# VFD-IV-25-5x7x2.net
KiCad netlist of a schematic drawn in EAGLE
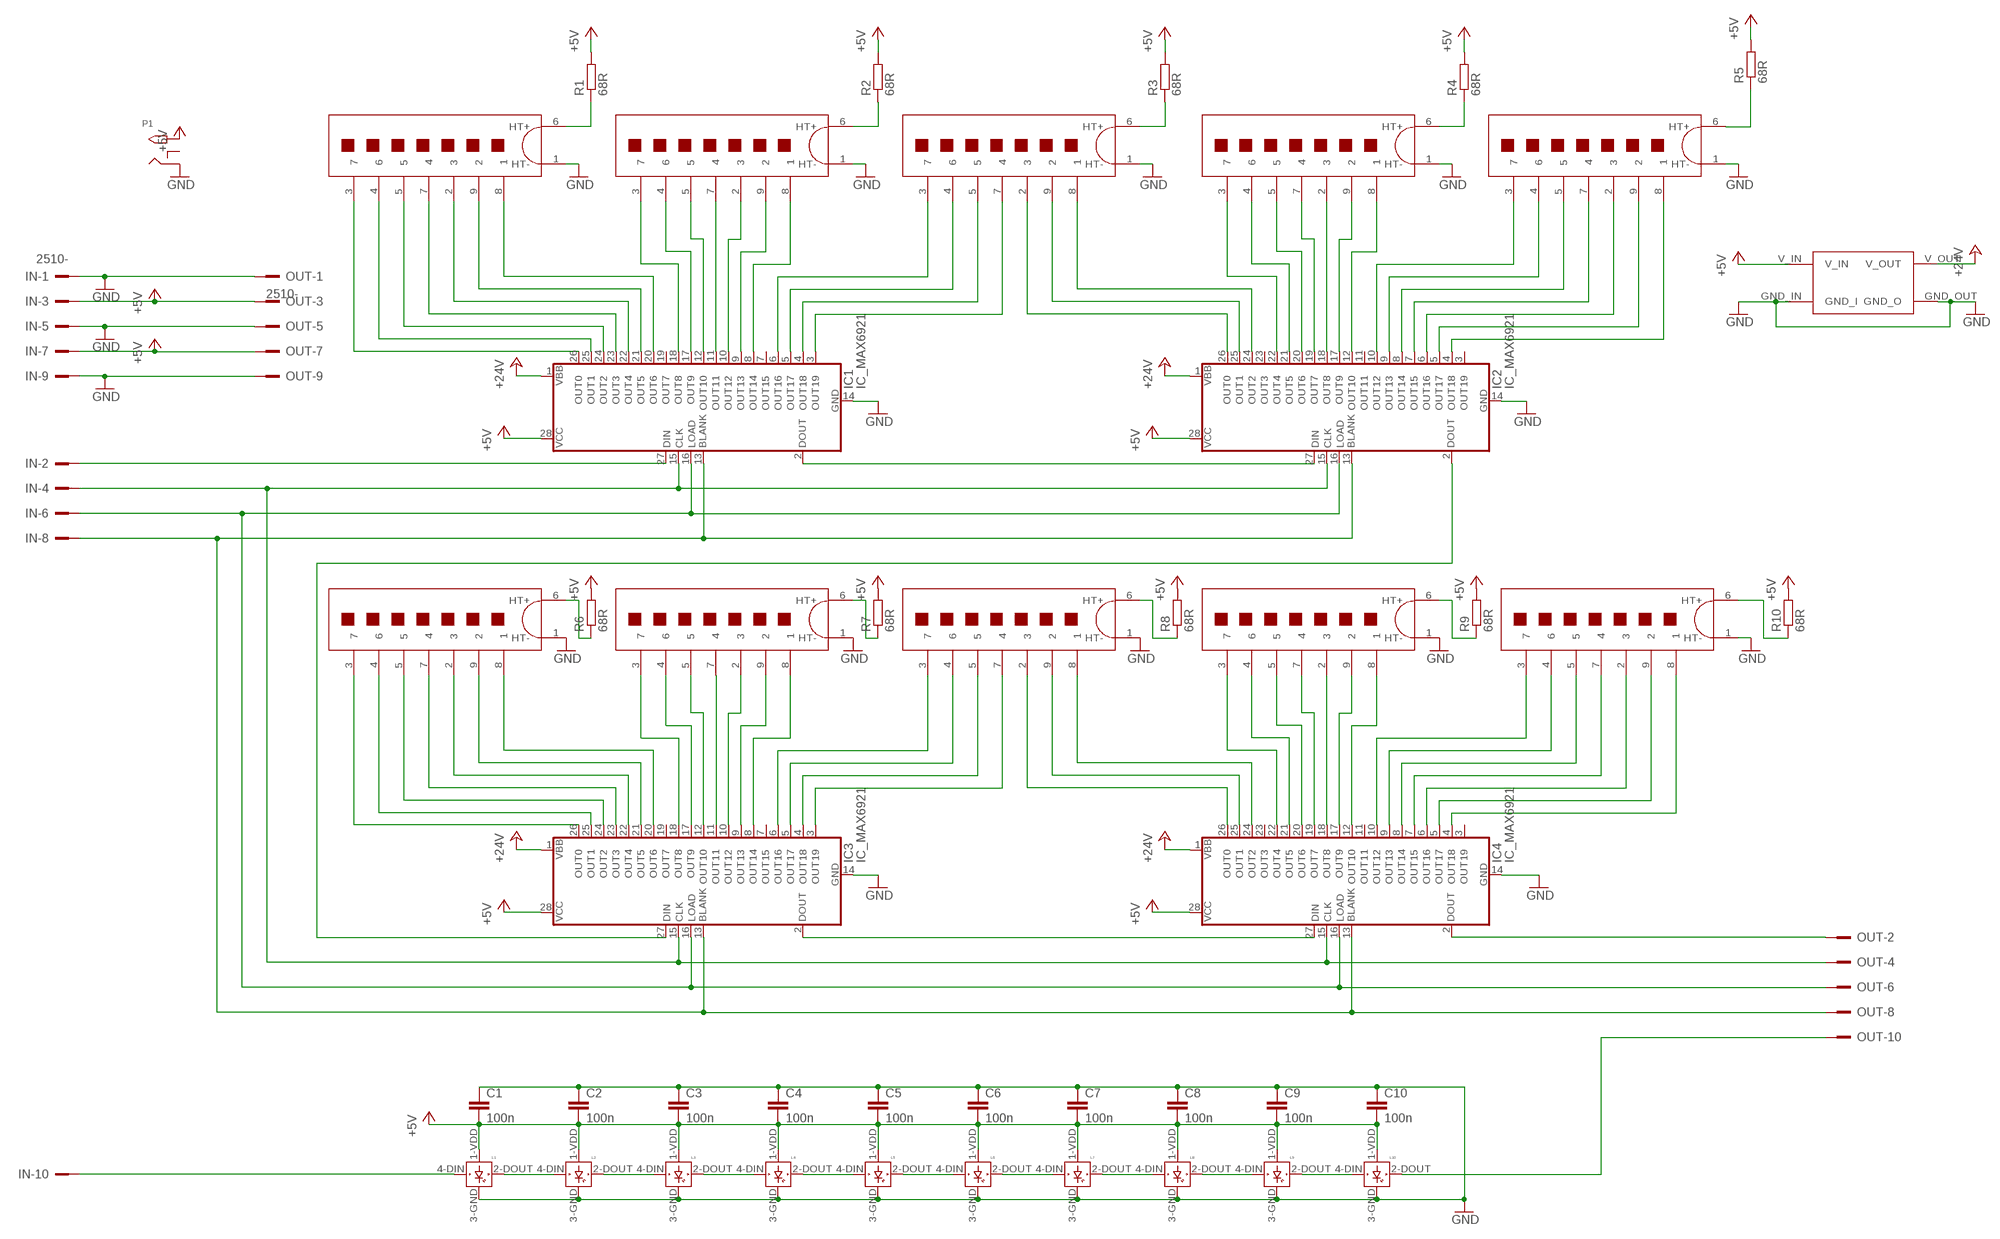
[diagram p0: schematic, sheet 1]

(export (version "E")
  (design (tool "Eeschema 10.0.6"))
  (components
    (comp (ref "1")
      (value "IV-25_DISP")
      (footprint "eagle-import:IV-25")
      (libsource (lib "eagle-import") (part "IV-25_DISP"))
    )
    (comp (ref "2")
      (value "IV-25_DISP")
      (footprint "eagle-import:IV-25")
      (libsource (lib "eagle-import") (part "IV-25_DISP"))
    )
    (comp (ref "3")
      (value "IV-25_DISP")
      (footprint "eagle-import:IV-25")
      (libsource (lib "eagle-import") (part "IV-25_DISP"))
    )
    (comp (ref "4")
      (value "IV-25_DISP")
      (footprint "eagle-import:IV-25")
      (libsource (lib "eagle-import") (part "IV-25_DISP"))
    )
    (comp (ref "5")
      (value "IV-25_DISP")
      (footprint "eagle-import:IV-25")
      (libsource (lib "eagle-import") (part "IV-25_DISP"))
    )
    (comp (ref "6")
      (value "IV-25_DISP")
      (footprint "eagle-import:IV-25")
      (libsource (lib "eagle-import") (part "IV-25_DISP"))
    )
    (comp (ref "7")
      (value "IV-25_DISP")
      (footprint "eagle-import:IV-25")
      (libsource (lib "eagle-import") (part "IV-25_DISP"))
    )
    (comp (ref "8")
      (value "IV-25_DISP")
      (footprint "eagle-import:IV-25")
      (libsource (lib "eagle-import") (part "IV-25_DISP"))
    )
    (comp (ref "9")
      (value "IV-25_DISP")
      (footprint "eagle-import:IV-25")
      (libsource (lib "eagle-import") (part "IV-25_DISP"))
    )
    (comp (ref "10")
      (value "IV-25_DISP")
      (footprint "eagle-import:IV-25")
      (libsource (lib "eagle-import") (part "IV-25_DISP"))
    )
    (comp (ref "C1")
      (value "100n")
      (footprint "eagle-import:C050-025X075")
      (libsource (lib "eagle-import") (part "C-EU050-025X075"))
    )
    (comp (ref "C2")
      (value "100n")
      (footprint "eagle-import:C050-025X075")
      (libsource (lib "eagle-import") (part "C-EU050-025X075"))
    )
    (comp (ref "C3")
      (value "100n")
      (footprint "eagle-import:C050-025X075")
      (libsource (lib "eagle-import") (part "C-EU050-025X075"))
    )
    (comp (ref "C4")
      (value "100n")
      (footprint "eagle-import:C050-025X075")
      (libsource (lib "eagle-import") (part "C-EU050-025X075"))
    )
    (comp (ref "C5")
      (value "100n")
      (footprint "eagle-import:C050-025X075")
      (libsource (lib "eagle-import") (part "C-EU050-025X075"))
    )
    (comp (ref "C6")
      (value "100n")
      (footprint "eagle-import:C050-025X075")
      (libsource (lib "eagle-import") (part "C-EU050-025X075"))
    )
    (comp (ref "C7")
      (value "100n")
      (footprint "eagle-import:C050-025X075")
      (libsource (lib "eagle-import") (part "C-EU050-025X075"))
    )
    (comp (ref "C8")
      (value "100n")
      (footprint "eagle-import:C050-025X075")
      (libsource (lib "eagle-import") (part "C-EU050-025X075"))
    )
    (comp (ref "C9")
      (value "100n")
      (footprint "eagle-import:C050-025X075")
      (libsource (lib "eagle-import") (part "C-EU050-025X075"))
    )
    (comp (ref "C10")
      (value "100n")
      (footprint "eagle-import:C050-025X075")
      (libsource (lib "eagle-import") (part "C-EU050-025X075"))
    )
    (comp (ref "IC1")
      (value "IC_MAX6921")
      (footprint "eagle-import:S28")
      (libsource (lib "eagle-import") (part "IC_MAX6921"))
    )
    (comp (ref "IC2")
      (value "IC_MAX6921")
      (footprint "eagle-import:S28")
      (libsource (lib "eagle-import") (part "IC_MAX6921"))
    )
    (comp (ref "IC3")
      (value "IC_MAX6921")
      (footprint "eagle-import:S28")
      (libsource (lib "eagle-import") (part "IC_MAX6921"))
    )
    (comp (ref "IC4")
      (value "IC_MAX6921")
      (footprint "eagle-import:S28")
      (libsource (lib "eagle-import") (part "IC_MAX6921"))
    )
    (comp (ref "IN")
      (value "2510-")
      (footprint "eagle-import:PAK100_2500-10")
      (fields (field (name "MF") "3M") (field (name "MPN") "2510-6002UB"))
      (libsource (lib "eagle-import") (part "2510-"))
    )
    (comp (ref "L1")
      (value "WS2812B")
      (footprint "eagle-import:WS2812B")
      (libsource (lib "eagle-import") (part "WS2812B"))
    )
    (comp (ref "L2")
      (value "WS2812B")
      (footprint "eagle-import:WS2812B")
      (libsource (lib "eagle-import") (part "WS2812B"))
    )
    (comp (ref "L3")
      (value "WS2812B")
      (footprint "eagle-import:WS2812B")
      (libsource (lib "eagle-import") (part "WS2812B"))
    )
    (comp (ref "L4")
      (value "WS2812B")
      (footprint "eagle-import:WS2812B")
      (libsource (lib "eagle-import") (part "WS2812B"))
    )
    (comp (ref "L5")
      (value "WS2812B")
      (footprint "eagle-import:WS2812B")
      (libsource (lib "eagle-import") (part "WS2812B"))
    )
    (comp (ref "L6")
      (value "WS2812B")
      (footprint "eagle-import:WS2812B")
      (libsource (lib "eagle-import") (part "WS2812B"))
    )
    (comp (ref "L7")
      (value "WS2812B")
      (footprint "eagle-import:WS2812B")
      (libsource (lib "eagle-import") (part "WS2812B"))
    )
    (comp (ref "L8")
      (value "WS2812B")
      (footprint "eagle-import:WS2812B")
      (libsource (lib "eagle-import") (part "WS2812B"))
    )
    (comp (ref "L9")
      (value "WS2812B")
      (footprint "eagle-import:WS2812B")
      (libsource (lib "eagle-import") (part "WS2812B"))
    )
    (comp (ref "L10")
      (value "WS2812B")
      (footprint "eagle-import:WS2812B")
      (libsource (lib "eagle-import") (part "WS2812B"))
    )
    (comp (ref "OUT")
      (value "2510-")
      (footprint "eagle-import:PAK100_2500-10")
      (fields (field (name "MF") "3M") (field (name "MPN") "2510-6002UB"))
      (libsource (lib "eagle-import") (part "2510-"))
    )
    (comp (ref "P1")
      (value "2.1MMJACKTHM")
      (footprint "eagle-import:PJ-102A")
      (libsource (lib "eagle-import") (part "2.1MMJACKTHM"))
    )
    (comp (ref "R1")
      (value "68R")
      (footprint "eagle-import:0207_10")
      (libsource (lib "eagle-import") (part "R-EU_0207/10"))
    )
    (comp (ref "R2")
      (value "68R")
      (footprint "eagle-import:0207_10")
      (libsource (lib "eagle-import") (part "R-EU_0207/10"))
    )
    (comp (ref "R3")
      (value "68R")
      (footprint "eagle-import:0207_10")
      (libsource (lib "eagle-import") (part "R-EU_0207/10"))
    )
    (comp (ref "R4")
      (value "68R")
      (footprint "eagle-import:0207_10")
      (libsource (lib "eagle-import") (part "R-EU_0207/10"))
    )
    (comp (ref "R5")
      (value "68R")
      (footprint "eagle-import:0207_10")
      (libsource (lib "eagle-import") (part "R-EU_0207/10"))
    )
    (comp (ref "R6")
      (value "68R")
      (footprint "eagle-import:0207_10")
      (libsource (lib "eagle-import") (part "R-EU_0207/10"))
    )
    (comp (ref "R7")
      (value "68R")
      (footprint "eagle-import:0207_10")
      (libsource (lib "eagle-import") (part "R-EU_0207/10"))
    )
    (comp (ref "R8")
      (value "68R")
      (footprint "eagle-import:0207_10")
      (libsource (lib "eagle-import") (part "R-EU_0207/10"))
    )
    (comp (ref "R9")
      (value "68R")
      (footprint "eagle-import:0207_10")
      (libsource (lib "eagle-import") (part "R-EU_0207/10"))
    )
    (comp (ref "R10")
      (value "68R")
      (footprint "eagle-import:0207_10")
      (libsource (lib "eagle-import") (part "R-EU_0207/10"))
    )
    (comp (ref "U$11")
      (value "STEP_UP_MODULE")
      (footprint "eagle-import:STEP_UP_MODULE")
      (libsource (lib "eagle-import") (part "STEP_UP_MODULE"))
    )
  )
  (nets
    (net (code "1") (name "+5V") (class "Default")
      (node (ref "C1") (pin "2") (pinfunction "2_2") (pintype "passive"))
      (node (ref "C10") (pin "2") (pinfunction "2_2") (pintype "passive"))
      (node (ref "C2") (pin "2") (pinfunction "2_2") (pintype "passive"))
      (node (ref "C3") (pin "2") (pinfunction "2_2") (pintype "passive"))
      (node (ref "C4") (pin "2") (pinfunction "2_2") (pintype "passive"))
      (node (ref "C5") (pin "2") (pinfunction "2_2") (pintype "passive"))
      (node (ref "C6") (pin "2") (pinfunction "2_2") (pintype "passive"))
      (node (ref "C7") (pin "2") (pinfunction "2_2") (pintype "passive"))
      (node (ref "C8") (pin "2") (pinfunction "2_2") (pintype "passive"))
      (node (ref "C9") (pin "2") (pinfunction "2_2") (pintype "passive"))
      (node (ref "IC1") (pin "28") (pinfunction "VCC_28") (pintype "power_in"))
      (node (ref "IC2") (pin "28") (pinfunction "VCC_28") (pintype "power_in"))
      (node (ref "IC3") (pin "28") (pinfunction "VCC_28") (pintype "power_in"))
      (node (ref "IC4") (pin "28") (pinfunction "VCC_28") (pintype "power_in"))
      (node (ref "IN") (pin "3") (pinfunction "KL_3") (pintype "passive"))
      (node (ref "IN") (pin "7") (pinfunction "KL_7") (pintype "passive"))
      (node (ref "L1") (pin "1-VDD") (pinfunction "VDD_1-VDD") (pintype "bidirectional"))
      (node (ref "L10") (pin "1-VDD") (pinfunction "VDD_1-VDD") (pintype "bidirectional"))
      (node (ref "L2") (pin "1-VDD") (pinfunction "VDD_1-VDD") (pintype "bidirectional"))
      (node (ref "L3") (pin "1-VDD") (pinfunction "VDD_1-VDD") (pintype "bidirectional"))
      (node (ref "L4") (pin "1-VDD") (pinfunction "VDD_1-VDD") (pintype "bidirectional"))
      (node (ref "L5") (pin "1-VDD") (pinfunction "VDD_1-VDD") (pintype "bidirectional"))
      (node (ref "L6") (pin "1-VDD") (pinfunction "VDD_1-VDD") (pintype "bidirectional"))
      (node (ref "L7") (pin "1-VDD") (pinfunction "VDD_1-VDD") (pintype "bidirectional"))
      (node (ref "L8") (pin "1-VDD") (pinfunction "VDD_1-VDD") (pintype "bidirectional"))
      (node (ref "L9") (pin "1-VDD") (pinfunction "VDD_1-VDD") (pintype "bidirectional"))
      (node (ref "OUT") (pin "3") (pinfunction "KL_3") (pintype "passive"))
      (node (ref "OUT") (pin "7") (pinfunction "KL_7") (pintype "passive"))
      (node (ref "P1") (pin "TIP") (pinfunction "TIP_TIP") (pintype "bidirectional"))
      (node (ref "R1") (pin "2") (pinfunction "2_2") (pintype "passive"))
      (node (ref "R10") (pin "2") (pinfunction "2_2") (pintype "passive"))
      (node (ref "R2") (pin "2") (pinfunction "2_2") (pintype "passive"))
      (node (ref "R3") (pin "2") (pinfunction "2_2") (pintype "passive"))
      (node (ref "R4") (pin "2") (pinfunction "2_2") (pintype "passive"))
      (node (ref "R5") (pin "2") (pinfunction "2_2") (pintype "passive"))
      (node (ref "R6") (pin "2") (pinfunction "2_2") (pintype "passive"))
      (node (ref "R7") (pin "2") (pinfunction "2_2") (pintype "passive"))
      (node (ref "R8") (pin "2") (pinfunction "2_2") (pintype "passive"))
      (node (ref "R9") (pin "2") (pinfunction "2_2") (pintype "passive"))
      (node (ref "U$11") (pin "V_IN") (pinfunction "V_IN_V_IN") (pintype "power_in"))
    )
    (net (code "2") (name "+24V") (class "Default")
      (node (ref "IC1") (pin "1") (pinfunction "VBB_1") (pintype "power_in"))
      (node (ref "IC2") (pin "1") (pinfunction "VBB_1") (pintype "power_in"))
      (node (ref "IC3") (pin "1") (pinfunction "VBB_1") (pintype "power_in"))
      (node (ref "IC4") (pin "1") (pinfunction "VBB_1") (pintype "power_in"))
      (node (ref "U$11") (pin "V_OUT") (pinfunction "V_OUT_V_OUT") (pintype "power_in"))
    )
    (net (code "3") (name "GND") (class "Default")
      (node (ref "1") (pin "1") (pinfunction "HT-_1") (pintype "power_in"))
      (node (ref "10") (pin "1") (pinfunction "HT-_1") (pintype "power_in"))
      (node (ref "2") (pin "1") (pinfunction "HT-_1") (pintype "power_in"))
      (node (ref "3") (pin "1") (pinfunction "HT-_1") (pintype "power_in"))
      (node (ref "4") (pin "1") (pinfunction "HT-_1") (pintype "power_in"))
      (node (ref "5") (pin "1") (pinfunction "HT-_1") (pintype "power_in"))
      (node (ref "6") (pin "1") (pinfunction "HT-_1") (pintype "power_in"))
      (node (ref "7") (pin "1") (pinfunction "HT-_1") (pintype "power_in"))
      (node (ref "8") (pin "1") (pinfunction "HT-_1") (pintype "power_in"))
      (node (ref "9") (pin "1") (pinfunction "HT-_1") (pintype "power_in"))
      (node (ref "C1") (pin "1") (pinfunction "1_1") (pintype "passive"))
      (node (ref "C10") (pin "1") (pinfunction "1_1") (pintype "passive"))
      (node (ref "C2") (pin "1") (pinfunction "1_1") (pintype "passive"))
      (node (ref "C3") (pin "1") (pinfunction "1_1") (pintype "passive"))
      (node (ref "C4") (pin "1") (pinfunction "1_1") (pintype "passive"))
      (node (ref "C5") (pin "1") (pinfunction "1_1") (pintype "passive"))
      (node (ref "C6") (pin "1") (pinfunction "1_1") (pintype "passive"))
      (node (ref "C7") (pin "1") (pinfunction "1_1") (pintype "passive"))
      (node (ref "C8") (pin "1") (pinfunction "1_1") (pintype "passive"))
      (node (ref "C9") (pin "1") (pinfunction "1_1") (pintype "passive"))
      (node (ref "IC1") (pin "14") (pinfunction "GND_14") (pintype "power_in"))
      (node (ref "IC2") (pin "14") (pinfunction "GND_14") (pintype "power_in"))
      (node (ref "IC3") (pin "14") (pinfunction "GND_14") (pintype "power_in"))
      (node (ref "IC4") (pin "14") (pinfunction "GND_14") (pintype "power_in"))
      (node (ref "IN") (pin "1") (pinfunction "KL_1") (pintype "passive"))
      (node (ref "IN") (pin "5") (pinfunction "KL_5") (pintype "passive"))
      (node (ref "IN") (pin "9") (pinfunction "KL_9") (pintype "passive"))
      (node (ref "L1") (pin "3-GND") (pinfunction "GND_3-GND") (pintype "bidirectional"))
      (node (ref "L10") (pin "3-GND") (pinfunction "GND_3-GND") (pintype "bidirectional"))
      (node (ref "L2") (pin "3-GND") (pinfunction "GND_3-GND") (pintype "bidirectional"))
      (node (ref "L3") (pin "3-GND") (pinfunction "GND_3-GND") (pintype "bidirectional"))
      (node (ref "L4") (pin "3-GND") (pinfunction "GND_3-GND") (pintype "bidirectional"))
      (node (ref "L5") (pin "3-GND") (pinfunction "GND_3-GND") (pintype "bidirectional"))
      (node (ref "L6") (pin "3-GND") (pinfunction "GND_3-GND") (pintype "bidirectional"))
      (node (ref "L7") (pin "3-GND") (pinfunction "GND_3-GND") (pintype "bidirectional"))
      (node (ref "L8") (pin "3-GND") (pinfunction "GND_3-GND") (pintype "bidirectional"))
      (node (ref "L9") (pin "3-GND") (pinfunction "GND_3-GND") (pintype "bidirectional"))
      (node (ref "OUT") (pin "1") (pinfunction "KL_1") (pintype "passive"))
      (node (ref "OUT") (pin "5") (pinfunction "KL_5") (pintype "passive"))
      (node (ref "OUT") (pin "9") (pinfunction "KL_9") (pintype "passive"))
      (node (ref "P1") (pin "RING") (pinfunction "RING_RING") (pintype "bidirectional"))
      (node (ref "U$11") (pin "GND_IN") (pinfunction "GND_I_GND_IN") (pintype "power_in"))
      (node (ref "U$11") (pin "GND_OUT") (pinfunction "GND_O_GND_OUT") (pintype "power_in"))
    )
    (net (code "4") (name "Net-(1-1)") (class "Default")
      (node (ref "1") (pin "8") (pinfunction "1_8") (pintype "input"))
      (node (ref "IC1") (pin "20") (pinfunction "OUT6_20") (pintype "output"))
    )
    (net (code "5") (name "Net-(1-2)") (class "Default")
      (node (ref "1") (pin "9") (pinfunction "2_9") (pintype "input"))
      (node (ref "IC1") (pin "21") (pinfunction "OUT5_21") (pintype "output"))
    )
    (net (code "6") (name "Net-(1-3)") (class "Default")
      (node (ref "1") (pin "2") (pinfunction "3_2") (pintype "input"))
      (node (ref "IC1") (pin "22") (pinfunction "OUT4_22") (pintype "output"))
    )
    (net (code "7") (name "Net-(1-4)") (class "Default")
      (node (ref "1") (pin "7") (pinfunction "4_7") (pintype "input"))
      (node (ref "IC1") (pin "23") (pinfunction "OUT3_23") (pintype "output"))
    )
    (net (code "8") (name "Net-(1-6)") (class "Default")
      (node (ref "1") (pin "4") (pinfunction "6_4") (pintype "input"))
      (node (ref "IC1") (pin "25") (pinfunction "OUT1_25") (pintype "output"))
    )
    (net (code "9") (name "Net-(1-7)") (class "Default")
      (node (ref "1") (pin "3") (pinfunction "7_3") (pintype "input"))
      (node (ref "IC1") (pin "26") (pinfunction "OUT0_26") (pintype "output"))
    )
    (net (code "10") (name "Net-(1-HT+)") (class "Default")
      (node (ref "1") (pin "6") (pinfunction "HT+_6") (pintype "power_in"))
      (node (ref "R1") (pin "1") (pinfunction "1_1") (pintype "passive"))
    )
    (net (code "11") (name "Net-(2-1)") (class "Default")
      (node (ref "2") (pin "8") (pinfunction "1_8") (pintype "input"))
      (node (ref "IC1") (pin "8") (pinfunction "OUT14_8") (pintype "output"))
    )
    (net (code "12") (name "Net-(2-2)") (class "Default")
      (node (ref "2") (pin "9") (pinfunction "2_9") (pintype "input"))
      (node (ref "IC1") (pin "9") (pinfunction "OUT13_9") (pintype "output"))
    )
    (net (code "13") (name "Net-(2-3)") (class "Default")
      (node (ref "2") (pin "2") (pinfunction "3_2") (pintype "input"))
      (node (ref "IC1") (pin "10") (pinfunction "OUT12_10") (pintype "output"))
    )
    (net (code "14") (name "Net-(2-4)") (class "Default")
      (node (ref "2") (pin "7") (pinfunction "4_7") (pintype "input"))
      (node (ref "IC1") (pin "11") (pinfunction "OUT11_11") (pintype "output"))
    )
    (net (code "15") (name "Net-(2-6)") (class "Default")
      (node (ref "2") (pin "4") (pinfunction "6_4") (pintype "input"))
      (node (ref "IC1") (pin "17") (pinfunction "OUT9_17") (pintype "output"))
    )
    (net (code "16") (name "Net-(2-7)") (class "Default")
      (node (ref "2") (pin "3") (pinfunction "7_3") (pintype "input"))
      (node (ref "IC1") (pin "18") (pinfunction "OUT8_18") (pintype "output"))
    )
    (net (code "17") (name "Net-(2-HT+)") (class "Default")
      (node (ref "2") (pin "6") (pinfunction "HT+_6") (pintype "power_in"))
      (node (ref "R2") (pin "1") (pinfunction "1_1") (pintype "passive"))
    )
    (net (code "18") (name "Net-(3-1)") (class "Default")
      (node (ref "3") (pin "8") (pinfunction "1_8") (pintype "input"))
      (node (ref "IC2") (pin "24") (pinfunction "OUT2_24") (pintype "output"))
    )
    (net (code "19") (name "Net-(3-2)") (class "Default")
      (node (ref "3") (pin "9") (pinfunction "2_9") (pintype "input"))
      (node (ref "IC2") (pin "25") (pinfunction "OUT1_25") (pintype "output"))
    )
    (net (code "20") (name "Net-(3-3)") (class "Default")
      (node (ref "3") (pin "2") (pinfunction "3_2") (pintype "input"))
      (node (ref "IC2") (pin "26") (pinfunction "OUT0_26") (pintype "output"))
    )
    (net (code "21") (name "Net-(3-4)") (class "Default")
      (node (ref "3") (pin "7") (pinfunction "4_7") (pintype "input"))
      (node (ref "IC1") (pin "3") (pinfunction "OUT19_3") (pintype "output"))
    )
    (net (code "22") (name "Net-(3-6)") (class "Default")
      (node (ref "3") (pin "4") (pinfunction "6_4") (pintype "input"))
      (node (ref "IC1") (pin "5") (pinfunction "OUT17_5") (pintype "output"))
    )
    (net (code "23") (name "Net-(3-7)") (class "Default")
      (node (ref "3") (pin "3") (pinfunction "7_3") (pintype "input"))
      (node (ref "IC1") (pin "6") (pinfunction "OUT16_6") (pintype "output"))
    )
    (net (code "24") (name "Net-(3-HT+)") (class "Default")
      (node (ref "3") (pin "6") (pinfunction "HT+_6") (pintype "power_in"))
      (node (ref "R3") (pin "1") (pinfunction "1_1") (pintype "passive"))
    )
    (net (code "25") (name "Net-(4-1)") (class "Default")
      (node (ref "4") (pin "8") (pinfunction "1_8") (pintype "input"))
      (node (ref "IC2") (pin "12") (pinfunction "OUT10_12") (pintype "output"))
    )
    (net (code "26") (name "Net-(4-2)") (class "Default")
      (node (ref "4") (pin "9") (pinfunction "2_9") (pintype "input"))
      (node (ref "IC2") (pin "17") (pinfunction "OUT9_17") (pintype "output"))
    )
    (net (code "27") (name "Net-(4-3)") (class "Default")
      (node (ref "4") (pin "2") (pinfunction "3_2") (pintype "input"))
      (node (ref "IC2") (pin "18") (pinfunction "OUT8_18") (pintype "output"))
    )
    (net (code "28") (name "Net-(4-4)") (class "Default")
      (node (ref "4") (pin "7") (pinfunction "4_7") (pintype "input"))
      (node (ref "IC2") (pin "19") (pinfunction "OUT7_19") (pintype "output"))
    )
    (net (code "29") (name "Net-(4-6)") (class "Default")
      (node (ref "4") (pin "4") (pinfunction "6_4") (pintype "input"))
      (node (ref "IC2") (pin "21") (pinfunction "OUT5_21") (pintype "output"))
    )
    (net (code "30") (name "Net-(4-7)") (class "Default")
      (node (ref "4") (pin "3") (pinfunction "7_3") (pintype "input"))
      (node (ref "IC2") (pin "22") (pinfunction "OUT4_22") (pintype "output"))
    )
    (net (code "31") (name "Net-(4-HT+)") (class "Default")
      (node (ref "4") (pin "6") (pinfunction "HT+_6") (pintype "power_in"))
      (node (ref "R4") (pin "1") (pinfunction "1_1") (pintype "passive"))
    )
    (net (code "32") (name "Net-(5-1)") (class "Default")
      (node (ref "5") (pin "8") (pinfunction "1_8") (pintype "input"))
      (node (ref "IC2") (pin "4") (pinfunction "OUT18_4") (pintype "output"))
    )
    (net (code "33") (name "Net-(5-2)") (class "Default")
      (node (ref "5") (pin "9") (pinfunction "2_9") (pintype "input"))
      (node (ref "IC2") (pin "5") (pinfunction "OUT17_5") (pintype "output"))
    )
    (net (code "34") (name "Net-(5-3)") (class "Default")
      (node (ref "5") (pin "2") (pinfunction "3_2") (pintype "input"))
      (node (ref "IC2") (pin "6") (pinfunction "OUT16_6") (pintype "output"))
    )
    (net (code "35") (name "Net-(5-4)") (class "Default")
      (node (ref "5") (pin "7") (pinfunction "4_7") (pintype "input"))
      (node (ref "IC2") (pin "7") (pinfunction "OUT15_7") (pintype "output"))
    )
    (net (code "36") (name "Net-(5-6)") (class "Default")
      (node (ref "5") (pin "4") (pinfunction "6_4") (pintype "input"))
      (node (ref "IC2") (pin "9") (pinfunction "OUT13_9") (pintype "output"))
    )
    (net (code "37") (name "Net-(5-7)") (class "Default")
      (node (ref "5") (pin "3") (pinfunction "7_3") (pintype "input"))
      (node (ref "IC2") (pin "10") (pinfunction "OUT12_10") (pintype "output"))
    )
    (net (code "38") (name "Net-(5-HT+)") (class "Default")
      (node (ref "5") (pin "6") (pinfunction "HT+_6") (pintype "power_in"))
      (node (ref "R5") (pin "1") (pinfunction "1_1") (pintype "passive"))
    )
    (net (code "39") (name "Net-(6-1)") (class "Default")
      (node (ref "6") (pin "8") (pinfunction "1_8") (pintype "input"))
      (node (ref "IC3") (pin "20") (pinfunction "OUT6_20") (pintype "output"))
    )
    (net (code "40") (name "Net-(6-2)") (class "Default")
      (node (ref "6") (pin "9") (pinfunction "2_9") (pintype "input"))
      (node (ref "IC3") (pin "21") (pinfunction "OUT5_21") (pintype "output"))
    )
    (net (code "41") (name "Net-(6-3)") (class "Default")
      (node (ref "6") (pin "2") (pinfunction "3_2") (pintype "input"))
      (node (ref "IC3") (pin "22") (pinfunction "OUT4_22") (pintype "output"))
    )
    (net (code "42") (name "Net-(6-4)") (class "Default")
      (node (ref "6") (pin "7") (pinfunction "4_7") (pintype "input"))
      (node (ref "IC3") (pin "23") (pinfunction "OUT3_23") (pintype "output"))
    )
    (net (code "43") (name "Net-(6-6)") (class "Default")
      (node (ref "6") (pin "4") (pinfunction "6_4") (pintype "input"))
      (node (ref "IC3") (pin "25") (pinfunction "OUT1_25") (pintype "output"))
    )
    (net (code "44") (name "Net-(6-7)") (class "Default")
      (node (ref "6") (pin "3") (pinfunction "7_3") (pintype "input"))
      (node (ref "IC3") (pin "26") (pinfunction "OUT0_26") (pintype "output"))
    )
    (net (code "45") (name "Net-(6-HT+)") (class "Default")
      (node (ref "6") (pin "6") (pinfunction "HT+_6") (pintype "power_in"))
      (node (ref "R6") (pin "1") (pinfunction "1_1") (pintype "passive"))
    )
    (net (code "46") (name "Net-(7-1)") (class "Default")
      (node (ref "7") (pin "8") (pinfunction "1_8") (pintype "input"))
      (node (ref "IC3") (pin "8") (pinfunction "OUT14_8") (pintype "output"))
    )
    (net (code "47") (name "Net-(7-2)") (class "Default")
      (node (ref "7") (pin "9") (pinfunction "2_9") (pintype "input"))
      (node (ref "IC3") (pin "9") (pinfunction "OUT13_9") (pintype "output"))
    )
    (net (code "48") (name "Net-(7-3)") (class "Default")
      (node (ref "7") (pin "2") (pinfunction "3_2") (pintype "input"))
      (node (ref "IC3") (pin "10") (pinfunction "OUT12_10") (pintype "output"))
    )
    (net (code "49") (name "Net-(7-4)") (class "Default")
      (node (ref "7") (pin "7") (pinfunction "4_7") (pintype "input"))
      (node (ref "IC3") (pin "11") (pinfunction "OUT11_11") (pintype "output"))
    )
    (net (code "50") (name "Net-(7-6)") (class "Default")
      (node (ref "7") (pin "4") (pinfunction "6_4") (pintype "input"))
      (node (ref "IC3") (pin "17") (pinfunction "OUT9_17") (pintype "output"))
    )
    (net (code "51") (name "Net-(7-7)") (class "Default")
      (node (ref "7") (pin "3") (pinfunction "7_3") (pintype "input"))
      (node (ref "IC3") (pin "18") (pinfunction "OUT8_18") (pintype "output"))
    )
    (net (code "52") (name "Net-(7-HT+)") (class "Default")
      (node (ref "7") (pin "6") (pinfunction "HT+_6") (pintype "power_in"))
      (node (ref "R7") (pin "1") (pinfunction "1_1") (pintype "passive"))
    )
    (net (code "53") (name "Net-(8-1)") (class "Default")
      (node (ref "8") (pin "8") (pinfunction "1_8") (pintype "input"))
      (node (ref "IC4") (pin "24") (pinfunction "OUT2_24") (pintype "output"))
    )
    (net (code "54") (name "Net-(8-2)") (class "Default")
      (node (ref "8") (pin "9") (pinfunction "2_9") (pintype "input"))
      (node (ref "IC4") (pin "25") (pinfunction "OUT1_25") (pintype "output"))
    )
    (net (code "55") (name "Net-(8-3)") (class "Default")
      (node (ref "8") (pin "2") (pinfunction "3_2") (pintype "input"))
      (node (ref "IC4") (pin "26") (pinfunction "OUT0_26") (pintype "output"))
    )
    (net (code "56") (name "Net-(8-4)") (class "Default")
      (node (ref "8") (pin "7") (pinfunction "4_7") (pintype "input"))
      (node (ref "IC3") (pin "3") (pinfunction "OUT19_3") (pintype "output"))
    )
    (net (code "57") (name "Net-(8-6)") (class "Default")
      (node (ref "8") (pin "4") (pinfunction "6_4") (pintype "input"))
      (node (ref "IC3") (pin "5") (pinfunction "OUT17_5") (pintype "output"))
    )
    (net (code "58") (name "Net-(8-7)") (class "Default")
      (node (ref "8") (pin "3") (pinfunction "7_3") (pintype "input"))
      (node (ref "IC3") (pin "6") (pinfunction "OUT16_6") (pintype "output"))
    )
    (net (code "59") (name "Net-(8-HT+)") (class "Default")
      (node (ref "8") (pin "6") (pinfunction "HT+_6") (pintype "power_in"))
      (node (ref "R8") (pin "1") (pinfunction "1_1") (pintype "passive"))
    )
    (net (code "60") (name "Net-(9-1)") (class "Default")
      (node (ref "9") (pin "8") (pinfunction "1_8") (pintype "input"))
      (node (ref "IC4") (pin "12") (pinfunction "OUT10_12") (pintype "output"))
    )
    (net (code "61") (name "Net-(9-2)") (class "Default")
      (node (ref "9") (pin "9") (pinfunction "2_9") (pintype "input"))
      (node (ref "IC4") (pin "17") (pinfunction "OUT9_17") (pintype "output"))
    )
    (net (code "62") (name "Net-(9-3)") (class "Default")
      (node (ref "9") (pin "2") (pinfunction "3_2") (pintype "input"))
      (node (ref "IC4") (pin "18") (pinfunction "OUT8_18") (pintype "output"))
    )
    (net (code "63") (name "Net-(9-4)") (class "Default")
      (node (ref "9") (pin "7") (pinfunction "4_7") (pintype "input"))
      (node (ref "IC4") (pin "19") (pinfunction "OUT7_19") (pintype "output"))
    )
    (net (code "64") (name "Net-(9-6)") (class "Default")
      (node (ref "9") (pin "4") (pinfunction "6_4") (pintype "input"))
      (node (ref "IC4") (pin "21") (pinfunction "OUT5_21") (pintype "output"))
    )
    (net (code "65") (name "Net-(9-7)") (class "Default")
      (node (ref "9") (pin "3") (pinfunction "7_3") (pintype "input"))
      (node (ref "IC4") (pin "22") (pinfunction "OUT4_22") (pintype "output"))
    )
    (net (code "66") (name "Net-(9-HT+)") (class "Default")
      (node (ref "9") (pin "6") (pinfunction "HT+_6") (pintype "power_in"))
      (node (ref "R9") (pin "1") (pinfunction "1_1") (pintype "passive"))
    )
    (net (code "67") (name "Net-(10-1)") (class "Default")
      (node (ref "10") (pin "8") (pinfunction "1_8") (pintype "input"))
      (node (ref "IC4") (pin "4") (pinfunction "OUT18_4") (pintype "output"))
    )
    (net (code "68") (name "Net-(10-2)") (class "Default")
      (node (ref "10") (pin "9") (pinfunction "2_9") (pintype "input"))
      (node (ref "IC4") (pin "5") (pinfunction "OUT17_5") (pintype "output"))
    )
    (net (code "69") (name "Net-(10-3)") (class "Default")
      (node (ref "10") (pin "2") (pinfunction "3_2") (pintype "input"))
      (node (ref "IC4") (pin "6") (pinfunction "OUT16_6") (pintype "output"))
    )
    (net (code "70") (name "Net-(10-4)") (class "Default")
      (node (ref "10") (pin "7") (pinfunction "4_7") (pintype "input"))
      (node (ref "IC4") (pin "7") (pinfunction "OUT15_7") (pintype "output"))
    )
    (net (code "71") (name "Net-(10-6)") (class "Default")
      (node (ref "10") (pin "4") (pinfunction "6_4") (pintype "input"))
      (node (ref "IC4") (pin "9") (pinfunction "OUT13_9") (pintype "output"))
    )
    (net (code "72") (name "Net-(10-7)") (class "Default")
      (node (ref "10") (pin "3") (pinfunction "7_3") (pintype "input"))
      (node (ref "IC4") (pin "10") (pinfunction "OUT12_10") (pintype "output"))
    )
    (net (code "73") (name "Net-(10-HT+)") (class "Default")
      (node (ref "10") (pin "6") (pinfunction "HT+_6") (pintype "power_in"))
      (node (ref "R10") (pin "1") (pinfunction "1_1") (pintype "passive"))
    )
    (net (code "74") (name "Net-(IC1-BLANK)") (class "Default")
      (node (ref "IC1") (pin "13") (pinfunction "BLANK_13") (pintype "input"))
      (node (ref "IC2") (pin "13") (pinfunction "BLANK_13") (pintype "input"))
      (node (ref "IC3") (pin "13") (pinfunction "BLANK_13") (pintype "input"))
      (node (ref "IC4") (pin "13") (pinfunction "BLANK_13") (pintype "input"))
      (node (ref "IN") (pin "8") (pinfunction "KL_8") (pintype "passive"))
      (node (ref "OUT") (pin "8") (pinfunction "KL_8") (pintype "passive"))
    )
    (net (code "75") (name "Net-(IC1-CLK)") (class "Default")
      (node (ref "IC1") (pin "15") (pinfunction "CLK_15") (pintype "input"))
      (node (ref "IC2") (pin "15") (pinfunction "CLK_15") (pintype "input"))
      (node (ref "IC3") (pin "15") (pinfunction "CLK_15") (pintype "input"))
      (node (ref "IC4") (pin "15") (pinfunction "CLK_15") (pintype "input"))
      (node (ref "IN") (pin "4") (pinfunction "KL_4") (pintype "passive"))
      (node (ref "OUT") (pin "4") (pinfunction "KL_4") (pintype "passive"))
    )
    (net (code "76") (name "Net-(IC1-DIN)") (class "Default")
      (node (ref "IC1") (pin "27") (pinfunction "DIN_27") (pintype "input"))
      (node (ref "IN") (pin "2") (pinfunction "KL_2") (pintype "passive"))
    )
    (net (code "77") (name "Net-(IC1-DOUT)") (class "Default")
      (node (ref "IC1") (pin "2") (pinfunction "DOUT_2") (pintype "output"))
      (node (ref "IC2") (pin "27") (pinfunction "DIN_27") (pintype "input"))
    )
    (net (code "78") (name "Net-(IC1-LOAD)") (class "Default")
      (node (ref "IC1") (pin "16") (pinfunction "LOAD_16") (pintype "input"))
      (node (ref "IC2") (pin "16") (pinfunction "LOAD_16") (pintype "input"))
      (node (ref "IC3") (pin "16") (pinfunction "LOAD_16") (pintype "input"))
      (node (ref "IC4") (pin "16") (pinfunction "LOAD_16") (pintype "input"))
      (node (ref "IN") (pin "6") (pinfunction "KL_6") (pintype "passive"))
      (node (ref "OUT") (pin "6") (pinfunction "KL_6") (pintype "passive"))
    )
    (net (code "79") (name "Net-(IC1-OUT2)") (class "Default")
      (node (ref "1") (pin "5") (pinfunction "5_5") (pintype "input"))
      (node (ref "IC1") (pin "24") (pinfunction "OUT2_24") (pintype "output"))
    )
    (net (code "80") (name "Net-(IC1-OUT10)") (class "Default")
      (node (ref "2") (pin "5") (pinfunction "5_5") (pintype "input"))
      (node (ref "IC1") (pin "12") (pinfunction "OUT10_12") (pintype "output"))
    )
    (net (code "81") (name "Net-(IC1-OUT18)") (class "Default")
      (node (ref "3") (pin "5") (pinfunction "5_5") (pintype "input"))
      (node (ref "IC1") (pin "4") (pinfunction "OUT18_4") (pintype "output"))
    )
    (net (code "82") (name "Net-(IC2-DOUT)") (class "Default")
      (node (ref "IC2") (pin "2") (pinfunction "DOUT_2") (pintype "output"))
      (node (ref "IC3") (pin "27") (pinfunction "DIN_27") (pintype "input"))
    )
    (net (code "83") (name "Net-(IC2-OUT6)") (class "Default")
      (node (ref "4") (pin "5") (pinfunction "5_5") (pintype "input"))
      (node (ref "IC2") (pin "20") (pinfunction "OUT6_20") (pintype "output"))
    )
    (net (code "84") (name "Net-(IC2-OUT14)") (class "Default")
      (node (ref "5") (pin "5") (pinfunction "5_5") (pintype "input"))
      (node (ref "IC2") (pin "8") (pinfunction "OUT14_8") (pintype "output"))
    )
    (net (code "85") (name "Net-(IC3-DOUT)") (class "Default")
      (node (ref "IC3") (pin "2") (pinfunction "DOUT_2") (pintype "output"))
      (node (ref "IC4") (pin "27") (pinfunction "DIN_27") (pintype "input"))
    )
    (net (code "86") (name "Net-(IC3-OUT2)") (class "Default")
      (node (ref "6") (pin "5") (pinfunction "5_5") (pintype "input"))
      (node (ref "IC3") (pin "24") (pinfunction "OUT2_24") (pintype "output"))
    )
    (net (code "87") (name "Net-(IC3-OUT10)") (class "Default")
      (node (ref "7") (pin "5") (pinfunction "5_5") (pintype "input"))
      (node (ref "IC3") (pin "12") (pinfunction "OUT10_12") (pintype "output"))
    )
    (net (code "88") (name "Net-(IC3-OUT18)") (class "Default")
      (node (ref "8") (pin "5") (pinfunction "5_5") (pintype "input"))
      (node (ref "IC3") (pin "4") (pinfunction "OUT18_4") (pintype "output"))
    )
    (net (code "89") (name "Net-(IC4-DOUT)") (class "Default")
      (node (ref "IC4") (pin "2") (pinfunction "DOUT_2") (pintype "output"))
      (node (ref "OUT") (pin "2") (pinfunction "KL_2") (pintype "passive"))
    )
    (net (code "90") (name "Net-(IC4-OUT6)") (class "Default")
      (node (ref "9") (pin "5") (pinfunction "5_5") (pintype "input"))
      (node (ref "IC4") (pin "20") (pinfunction "OUT6_20") (pintype "output"))
    )
    (net (code "91") (name "Net-(IC4-OUT14)") (class "Default")
      (node (ref "10") (pin "5") (pinfunction "5_5") (pintype "input"))
      (node (ref "IC4") (pin "8") (pinfunction "OUT14_8") (pintype "output"))
    )
    (net (code "92") (name "Net-(INB-KL)") (class "Default")
      (node (ref "IN") (pin "10") (pinfunction "KL_10") (pintype "passive"))
      (node (ref "L1") (pin "4-DIN") (pinfunction "DIN_4-DIN") (pintype "input"))
    )
    (net (code "93") (name "Net-(L1-DOUT)") (class "Default")
      (node (ref "L1") (pin "2-DOUT") (pinfunction "DOUT_2-DOUT") (pintype "output"))
      (node (ref "L2") (pin "4-DIN") (pinfunction "DIN_4-DIN") (pintype "input"))
    )
    (net (code "94") (name "Net-(L2-DOUT)") (class "Default")
      (node (ref "L2") (pin "2-DOUT") (pinfunction "DOUT_2-DOUT") (pintype "output"))
      (node (ref "L3") (pin "4-DIN") (pinfunction "DIN_4-DIN") (pintype "input"))
    )
    (net (code "95") (name "Net-(L3-DOUT)") (class "Default")
      (node (ref "L3") (pin "2-DOUT") (pinfunction "DOUT_2-DOUT") (pintype "output"))
      (node (ref "L4") (pin "4-DIN") (pinfunction "DIN_4-DIN") (pintype "input"))
    )
    (net (code "96") (name "Net-(L4-DOUT)") (class "Default")
      (node (ref "L4") (pin "2-DOUT") (pinfunction "DOUT_2-DOUT") (pintype "output"))
      (node (ref "L5") (pin "4-DIN") (pinfunction "DIN_4-DIN") (pintype "input"))
    )
    (net (code "97") (name "Net-(L5-DOUT)") (class "Default")
      (node (ref "L5") (pin "2-DOUT") (pinfunction "DOUT_2-DOUT") (pintype "output"))
      (node (ref "L6") (pin "4-DIN") (pinfunction "DIN_4-DIN") (pintype "input"))
    )
    (net (code "98") (name "Net-(L6-DOUT)") (class "Default")
      (node (ref "L6") (pin "2-DOUT") (pinfunction "DOUT_2-DOUT") (pintype "output"))
      (node (ref "L7") (pin "4-DIN") (pinfunction "DIN_4-DIN") (pintype "input"))
    )
    (net (code "99") (name "Net-(L7-DOUT)") (class "Default")
      (node (ref "L7") (pin "2-DOUT") (pinfunction "DOUT_2-DOUT") (pintype "output"))
      (node (ref "L8") (pin "4-DIN") (pinfunction "DIN_4-DIN") (pintype "input"))
    )
    (net (code "100") (name "Net-(L8-DOUT)") (class "Default")
      (node (ref "L8") (pin "2-DOUT") (pinfunction "DOUT_2-DOUT") (pintype "output"))
      (node (ref "L9") (pin "4-DIN") (pinfunction "DIN_4-DIN") (pintype "input"))
    )
    (net (code "101") (name "Net-(L10-DIN)") (class "Default")
      (node (ref "L10") (pin "4-DIN") (pinfunction "DIN_4-DIN") (pintype "input"))
      (node (ref "L9") (pin "2-DOUT") (pinfunction "DOUT_2-DOUT") (pintype "output"))
    )
    (net (code "102") (name "Net-(L10-DOUT)") (class "Default")
      (node (ref "L10") (pin "2-DOUT") (pinfunction "DOUT_2-DOUT") (pintype "output"))
      (node (ref "OUT") (pin "10") (pinfunction "KL_10") (pintype "passive"))
    )
    (net (code "103") (name "unconnected-(IC1-OUT7-Pad19)") (class "Default")
      (node (ref "IC1") (pin "19") (pinfunction "OUT7_19") (pintype "output"))
    )
    (net (code "104") (name "unconnected-(IC1-OUT15-Pad7)") (class "Default")
      (node (ref "IC1") (pin "7") (pinfunction "OUT15_7") (pintype "output"))
    )
    (net (code "105") (name "unconnected-(IC2-OUT3-Pad23)") (class "Default")
      (node (ref "IC2") (pin "23") (pinfunction "OUT3_23") (pintype "output"))
    )
    (net (code "106") (name "unconnected-(IC2-OUT11-Pad11)") (class "Default")
      (node (ref "IC2") (pin "11") (pinfunction "OUT11_11") (pintype "output"))
    )
    (net (code "107") (name "unconnected-(IC2-OUT19-Pad3)") (class "Default")
      (node (ref "IC2") (pin "3") (pinfunction "OUT19_3") (pintype "output"))
    )
    (net (code "108") (name "unconnected-(IC3-OUT7-Pad19)") (class "Default")
      (node (ref "IC3") (pin "19") (pinfunction "OUT7_19") (pintype "output"))
    )
    (net (code "109") (name "unconnected-(IC3-OUT15-Pad7)") (class "Default")
      (node (ref "IC3") (pin "7") (pinfunction "OUT15_7") (pintype "output"))
    )
    (net (code "110") (name "unconnected-(IC4-OUT3-Pad23)") (class "Default")
      (node (ref "IC4") (pin "23") (pinfunction "OUT3_23") (pintype "output"))
    )
    (net (code "111") (name "unconnected-(IC4-OUT11-Pad11)") (class "Default")
      (node (ref "IC4") (pin "11") (pinfunction "OUT11_11") (pintype "output"))
    )
    (net (code "112") (name "unconnected-(IC4-OUT19-Pad3)") (class "Default")
      (node (ref "IC4") (pin "3") (pinfunction "OUT19_3") (pintype "output"))
    )
    (net (code "113") (name "unconnected-(P1-PadRING_SW)") (class "Default")
      (node (ref "P1") (pin "RING_SW") (pinfunction "RING_SW_RING_SW") (pintype "bidirectional"))
    )
  )
)
